# RJ11_BoshBaro_HwellHyg.net
KiCad netlist of a schematic drawn in EAGLE
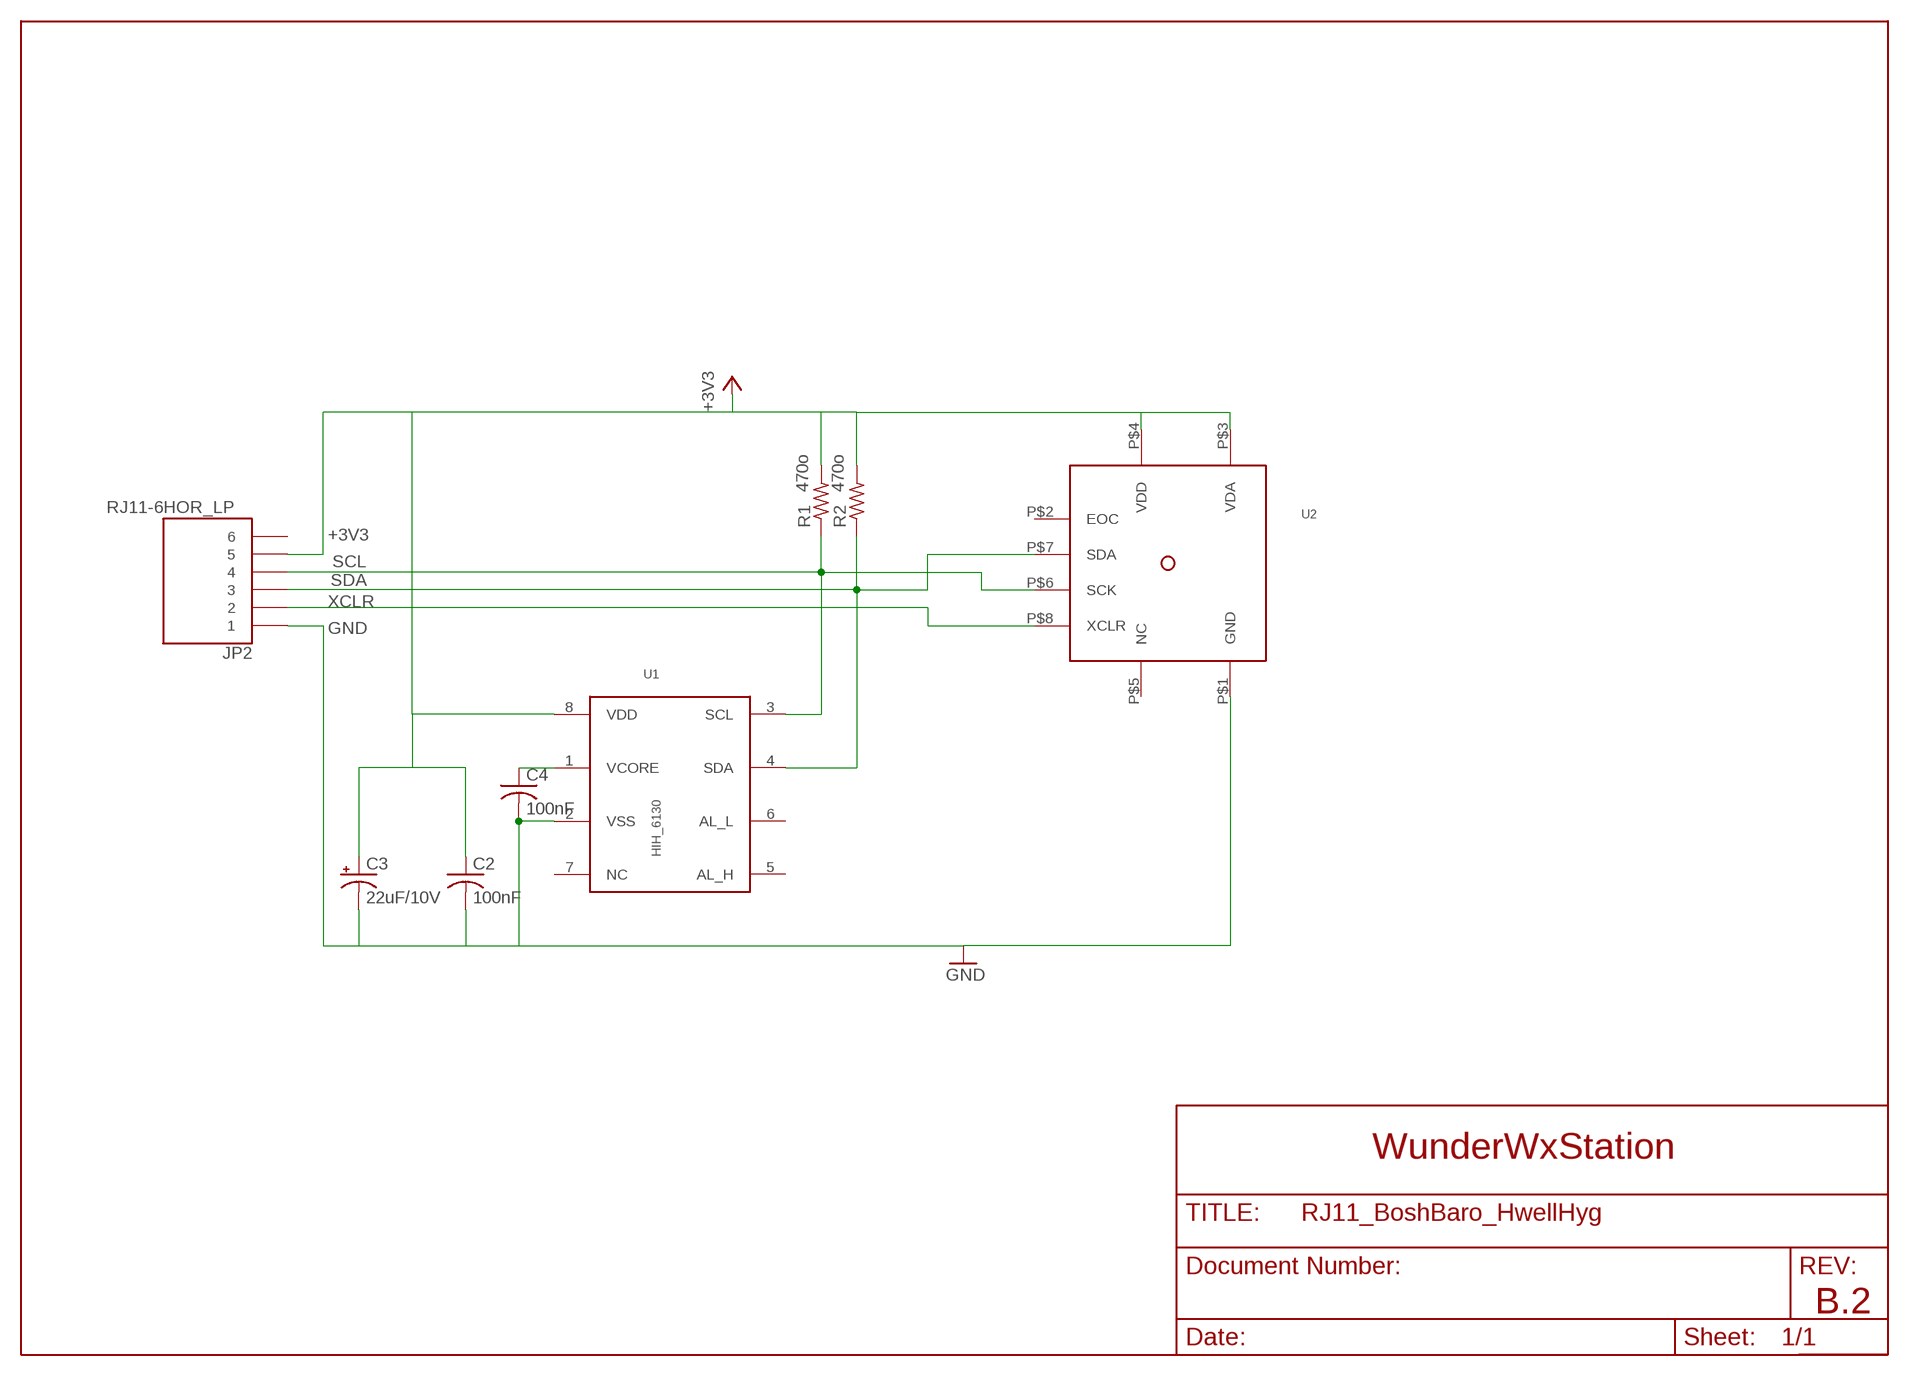
[diagram p0: schematic, sheet 1]

(export (version "E")
  (design (tool "Eeschema 10.0.6"))
  (components
    (comp (ref "C2")
      (value "100nF")
      (footprint "eagle-import:C0805K")
      (libsource (lib "eagle-import") (part "C-USC0805K"))
    )
    (comp (ref "C3")
      (value "22uF/10V")
      (footprint "eagle-import:SMC_B")
      (libsource (lib "eagle-import") (part "CPOL-USSMCB"))
    )
    (comp (ref "C4")
      (value "100nF")
      (footprint "eagle-import:C0805K")
      (libsource (lib "eagle-import") (part "C-USC0805K"))
    )
    (comp (ref "JP2")
      (value "RJ11-6HOR_LP")
      (footprint "eagle-import:RJ11_HOR_LP")
      (libsource (lib "eagle-import") (part "RJ11-6HOR_LP"))
    )
    (comp (ref "R1")
      (value "470o")
      (footprint "eagle-import:R0603")
      (libsource (lib "eagle-import") (part "R-US_R0603"))
    )
    (comp (ref "R2")
      (value "470o")
      (footprint "eagle-import:R0603")
      (libsource (lib "eagle-import") (part "R-US_R0603"))
    )
    (comp (ref "U1")
      (value "HIH_6130")
      (footprint "eagle-import:SOIC8")
      (libsource (lib "eagle-import") (part "HIH_6130"))
    )
    (comp (ref "U2")
      (value "BMP085")
      (footprint "eagle-import:LCC8")
      (libsource (lib "eagle-import") (part "BMP085"))
    )
  )
  (nets
    (net (code "1") (name "+3V3") (class "Default")
      (node (ref "C2") (pin "1") (pinfunction "1_1") (pintype "passive"))
      (node (ref "C3") (pin "+") (pinfunction "+_+") (pintype "passive"))
      (node (ref "JP2") (pin "P$5") (pinfunction "5_P$5") (pintype "bidirectional"))
      (node (ref "R1") (pin "2") (pinfunction "2_2") (pintype "passive"))
      (node (ref "R2") (pin "2") (pinfunction "2_2") (pintype "passive"))
      (node (ref "U1") (pin "8") (pinfunction "VDD_8") (pintype "bidirectional"))
      (node (ref "U2") (pin "P$3") (pinfunction "VDA_P$3") (pintype "power_in"))
      (node (ref "U2") (pin "P$4") (pinfunction "VDD_P$4") (pintype "power_in"))
    )
    (net (code "2") (name "/SCL") (class "Default")
      (node (ref "JP2") (pin "P$4") (pinfunction "4_P$4") (pintype "bidirectional"))
      (node (ref "R1") (pin "1") (pinfunction "1_1") (pintype "passive"))
      (node (ref "U1") (pin "3") (pinfunction "SCL_3") (pintype "bidirectional"))
      (node (ref "U2") (pin "P$6") (pinfunction "SCK_P$6") (pintype "input"))
    )
    (net (code "3") (name "/SDA") (class "Default")
      (node (ref "JP2") (pin "P$3") (pinfunction "3_P$3") (pintype "bidirectional"))
      (node (ref "R2") (pin "1") (pinfunction "1_1") (pintype "passive"))
      (node (ref "U1") (pin "4") (pinfunction "SDA_4") (pintype "bidirectional"))
      (node (ref "U2") (pin "P$7") (pinfunction "SDA_P$7") (pintype "bidirectional"))
    )
    (net (code "4") (name "/XCLR") (class "Default")
      (node (ref "JP2") (pin "P$2") (pinfunction "2_P$2") (pintype "bidirectional"))
      (node (ref "U2") (pin "P$8") (pinfunction "XCLR_P$8") (pintype "input"))
    )
    (net (code "5") (name "GND") (class "Default")
      (node (ref "C2") (pin "2") (pinfunction "2_2") (pintype "passive"))
      (node (ref "C3") (pin "-") (pinfunction "-_-") (pintype "passive"))
      (node (ref "C4") (pin "2") (pinfunction "2_2") (pintype "passive"))
      (node (ref "JP2") (pin "P$1") (pinfunction "1_P$1") (pintype "bidirectional"))
      (node (ref "U1") (pin "2") (pinfunction "VSS_2") (pintype "bidirectional"))
      (node (ref "U2") (pin "P$1") (pinfunction "GND_P$1") (pintype "power_in"))
    )
    (net (code "6") (name "Net-(U1-VCORE)") (class "Default")
      (node (ref "C4") (pin "1") (pinfunction "1_1") (pintype "passive"))
      (node (ref "U1") (pin "1") (pinfunction "VCORE_1") (pintype "bidirectional"))
    )
    (net (code "7") (name "unconnected-(JP2-6-PadP$6)") (class "Default")
      (node (ref "JP2") (pin "P$6") (pinfunction "6_P$6") (pintype "bidirectional"))
    )
    (net (code "8") (name "unconnected-(U1-AL_H-Pad5)") (class "Default")
      (node (ref "U1") (pin "5") (pinfunction "AL_H_5") (pintype "bidirectional"))
    )
    (net (code "9") (name "unconnected-(U1-AL_L-Pad6)") (class "Default")
      (node (ref "U1") (pin "6") (pinfunction "AL_L_6") (pintype "bidirectional"))
    )
    (net (code "10") (name "unconnected-(U1-NC-Pad7)") (class "Default")
      (node (ref "U1") (pin "7") (pinfunction "NC_7") (pintype "bidirectional"))
    )
    (net (code "11") (name "unconnected-(U2-EOC-PadP$2)") (class "Default")
      (node (ref "U2") (pin "P$2") (pinfunction "EOC_P$2") (pintype "output"))
    )
    (net (code "12") (name "unconnected-(U2-NC-PadP$5)") (class "Default")
      (node (ref "U2") (pin "P$5") (pinfunction "NC_P$5") (pintype "no_connect"))
    )
  )
)
